# SD.net
KiCad netlist of a schematic drawn in Altium Designer
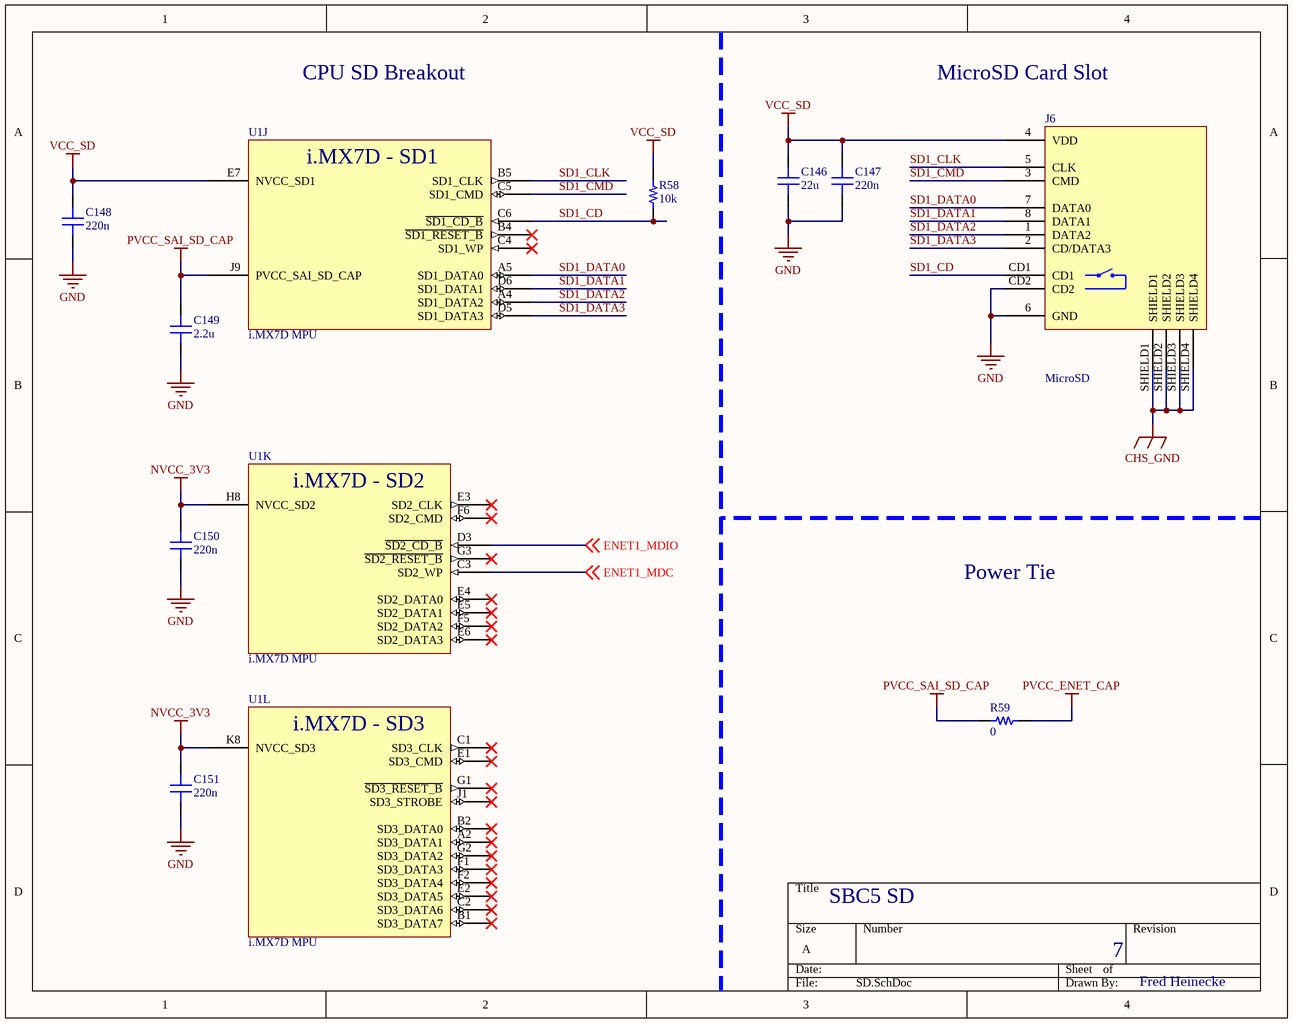
[diagram p0: SD.SchDoc]

(export (version "E")
  (design (tool "Eeschema 10.0.6"))
  (components
    (comp (ref "C146")
      (value "22u")
      (footprint "C0603")
      (description "0603 22 uF 10 V ±20% Tolerance X5R Multilayer Ceramic Chip Capacitor")
      (fields
        (field (name "MANUFACTURER") "Murata")
        (field (name "MANUFACTURER PART NUMBER") "GRM188R61A226ME15D")
      )
      (libsource (lib "SBC5") (part "GRM188R61A226ME15D"))
    )
    (comp (ref "C147")
      (value "220n")
      (footprint "C0201")
      (description "Cap Ceramic Monolithic 0.22uF 16VDC 10% SMD Paper T/R")
      (fields
        (field (name "MANUFACTURER") "Murata")
        (field (name "MANUFACTURER PART NUMBER") "GRM033R61C224KE14D")
      )
      (libsource (lib "SBC5") (part "GRM033R61C224KE14D"))
    )
    (comp (ref "C148")
      (value "220n")
      (footprint "C0201")
      (description "Cap Ceramic Monolithic 0.22uF 16VDC 10% SMD Paper T/R")
      (fields
        (field (name "MANUFACTURER") "Murata")
        (field (name "MANUFACTURER PART NUMBER") "GRM033R61C224KE14D")
      )
      (libsource (lib "SBC5") (part "GRM033R61C224KE14D"))
    )
    (comp (ref "C149")
      (value "2.2u")
      (footprint "C0402")
      (description "TAIYO YUDEN         LMK105BJ225MV-F            CERAMIC CAPACITOR, 2.2UF, 10V, X5R, 20%, 0402")
      (fields
        (field (name "MANUFACTURER") "Taiyo Yuden")
        (field (name "MANUFACTURER PART NUMBER") "LMK105BJ225MV-F")
      )
      (libsource (lib "SBC5") (part "LMK105BJ225MV-F"))
    )
    (comp (ref "C150")
      (value "220n")
      (footprint "C0201")
      (description "Cap Ceramic Monolithic 0.22uF 16VDC 10% SMD Paper T/R")
      (fields
        (field (name "MANUFACTURER") "Murata")
        (field (name "MANUFACTURER PART NUMBER") "GRM033R61C224KE14D")
      )
      (libsource (lib "SBC5") (part "GRM033R61C224KE14D"))
    )
    (comp (ref "C151")
      (value "220n")
      (footprint "C0201")
      (description "Cap Ceramic Monolithic 0.22uF 16VDC 10% SMD Paper T/R")
      (fields
        (field (name "MANUFACTURER") "Murata")
        (field (name "MANUFACTURER PART NUMBER") "GRM033R61C224KE14D")
      )
      (libsource (lib "SBC5") (part "GRM033R61C224KE14D"))
    )
    (comp (ref "J6")
      (value "MicroSD")
      (footprint "114-00841-68")
      (description "Conn; IC Socket; Micro SD; Right Angle; PCB Mount; MicroSD Ser.")
      (fields
        (field (name "MANUFACTURER") "Amphenol Commercial")
        (field (name "MANUFACTURER PART NUMBER") "1140084168")
      )
      (libsource (lib "SBC5") (part "1140084168"))
    )
    (comp (ref "R58")
      (value "10k")
      (footprint "R0201")
      (description "RES 10K OHM 1% 1/20W 0201")
      (fields
        (field (name "MANUFACTURER") "Stackpole Electronics")
        (field (name "MANUFACTURER PART NUMBER") "RMCF0201FT10K0")
      )
      (libsource (lib "SBC5") (part "RMCF0201FT10K0"))
    )
    (comp (ref "R59")
      (value "0")
      (footprint "R0402")
      (description "RES 0 OHM JUMPER 1/16W 0402")
      (fields
        (field (name "MANUFACTURER") "Stackpole Electronics")
        (field (name "MANUFACTURER PART NUMBER") "RMCF0402ZT0R00")
      )
      (libsource (lib "SBC5") (part "RMCF0402ZT0R00"))
    )
    (comp (ref "U1")
      (value "i.MX7D MPU")
      (footprint "BGA541C75P25X25_1900X1900X140")
      (description "Heterogeneous Multicore Processing Architecture")
      (fields
        (field (name "MANUFACTURER") "NXP Freescale")
        (field (name "MANUFACTURER PART NUMBER") "MCIMX7D2DVM12SD")
      )
      (libsource (lib "SBC5") (part "MCIMX7D2DVM12SD"))
    )
  )
  (nets
    (net (code "1") (name "/SD1_CD") (class "Default")
      (node (ref "J6") (pin "CD1") (pinfunction "CD1_CD1") (pintype "passive"))
      (node (ref "R58") (pin "1") (pinfunction "1_1") (pintype "passive"))
      (node (ref "U1") (pin "C6") (pinfunction "~{SD1_CD_B}_C6") (pintype "input"))
    )
    (net (code "2") (name "/SD1_CLK") (class "Default")
      (node (ref "J6") (pin "5") (pinfunction "CLK_5") (pintype "passive"))
      (node (ref "U1") (pin "B5") (pinfunction "SD1_CLK_B5") (pintype "output"))
    )
    (net (code "3") (name "/SD1_CMD") (class "Default")
      (node (ref "J6") (pin "3") (pinfunction "CMD_3") (pintype "passive"))
      (node (ref "U1") (pin "C5") (pinfunction "SD1_CMD_C5") (pintype "bidirectional"))
    )
    (net (code "4") (name "/SD1_DATA0") (class "Default")
      (node (ref "J6") (pin "7") (pinfunction "DATA0_7") (pintype "passive"))
      (node (ref "U1") (pin "A5") (pinfunction "SD1_DATA0_A5") (pintype "bidirectional"))
    )
    (net (code "5") (name "/SD1_DATA1") (class "Default")
      (node (ref "J6") (pin "8") (pinfunction "DATA1_8") (pintype "passive"))
      (node (ref "U1") (pin "D6") (pinfunction "SD1_DATA1_D6") (pintype "bidirectional"))
    )
    (net (code "6") (name "/SD1_DATA2") (class "Default")
      (node (ref "J6") (pin "1") (pinfunction "DATA2_1") (pintype "passive"))
      (node (ref "U1") (pin "A4") (pinfunction "SD1_DATA2_A4") (pintype "bidirectional"))
    )
    (net (code "7") (name "/SD1_DATA3") (class "Default")
      (node (ref "J6") (pin "2") (pinfunction "CD/DATA3_2") (pintype "passive"))
      (node (ref "U1") (pin "D5") (pinfunction "SD1_DATA3_D5") (pintype "bidirectional"))
    )
    (net (code "8") (name "CHS_GND") (class "Default")
      (node (ref "J6") (pin "SHIELD1") (pinfunction "SHIELD1_SHIELD1") (pintype "passive"))
      (node (ref "J6") (pin "SHIELD2") (pinfunction "SHIELD2_SHIELD2") (pintype "passive"))
      (node (ref "J6") (pin "SHIELD3") (pinfunction "SHIELD3_SHIELD3") (pintype "passive"))
      (node (ref "J6") (pin "SHIELD4") (pinfunction "SHIELD4_SHIELD4") (pintype "passive"))
    )
    (net (code "9") (name "ENET1_MDC") (class "Default")
      (node (ref "U1") (pin "C3") (pinfunction "SD2_WP_C3") (pintype "input"))
    )
    (net (code "10") (name "ENET1_MDIO") (class "Default")
      (node (ref "U1") (pin "D3") (pinfunction "~{SD2_CD_B}_D3") (pintype "input"))
    )
    (net (code "11") (name "GND") (class "Default")
      (node (ref "C146") (pin "1") (pinfunction "1_1") (pintype "passive"))
      (node (ref "C147") (pin "1") (pinfunction "1_1") (pintype "passive"))
      (node (ref "C148") (pin "1") (pinfunction "1_1") (pintype "passive"))
      (node (ref "C149") (pin "1") (pinfunction "1_1") (pintype "passive"))
      (node (ref "C150") (pin "1") (pinfunction "1_1") (pintype "passive"))
      (node (ref "C151") (pin "1") (pinfunction "1_1") (pintype "passive"))
      (node (ref "J6") (pin "6") (pinfunction "GND_6") (pintype "passive"))
      (node (ref "J6") (pin "CD2") (pinfunction "CD2_CD2") (pintype "passive"))
    )
    (net (code "12") (name "NVCC_3V3") (class "Default")
      (node (ref "C150") (pin "2") (pinfunction "2_2") (pintype "passive"))
      (node (ref "C151") (pin "2") (pinfunction "2_2") (pintype "passive"))
      (node (ref "U1") (pin "H8") (pinfunction "NVCC_SD2_H8") (pintype "power_in"))
      (node (ref "U1") (pin "K8") (pinfunction "NVCC_SD3_K8") (pintype "power_in"))
    )
    (net (code "13") (name "PVCC_ENET_CAP") (class "Default")
      (node (ref "R59") (pin "2") (pinfunction "2_2") (pintype "passive"))
    )
    (net (code "14") (name "PVCC_SAI_SD_CAP") (class "Default")
      (node (ref "C149") (pin "2") (pinfunction "2_2") (pintype "passive"))
      (node (ref "R59") (pin "1") (pinfunction "1_1") (pintype "passive"))
      (node (ref "U1") (pin "J9") (pinfunction "PVCC_SAI_SD_CAP_J9") (pintype "power_in"))
    )
    (net (code "15") (name "VCC_SD") (class "Default")
      (node (ref "C146") (pin "2") (pinfunction "2_2") (pintype "passive"))
      (node (ref "C147") (pin "2") (pinfunction "2_2") (pintype "passive"))
      (node (ref "C148") (pin "2") (pinfunction "2_2") (pintype "passive"))
      (node (ref "J6") (pin "4") (pinfunction "VDD_4") (pintype "passive"))
      (node (ref "R58") (pin "2") (pinfunction "2_2") (pintype "passive"))
      (node (ref "U1") (pin "E7") (pinfunction "NVCC_SD1_E7") (pintype "power_in"))
    )
    (net (code "16") (name "unconnected-(U1J-SD1_WP-PadC4)") (class "Default")
      (node (ref "U1") (pin "C4") (pinfunction "SD1_WP_C4") (pintype "input+no_connect"))
    )
    (net (code "17") (name "unconnected-(U1J-~{SD1_RESET_B}-PadB4)") (class "Default")
      (node (ref "U1") (pin "B4") (pinfunction "~{SD1_RESET_B}_B4") (pintype "output+no_connect"))
    )
    (net (code "18") (name "unconnected-(U1K-SD2_CLK-PadE3)") (class "Default")
      (node (ref "U1") (pin "E3") (pinfunction "SD2_CLK_E3") (pintype "output+no_connect"))
    )
    (net (code "19") (name "unconnected-(U1K-SD2_CMD-PadF6)") (class "Default")
      (node (ref "U1") (pin "F6") (pinfunction "SD2_CMD_F6") (pintype "bidirectional+no_connect"))
    )
    (net (code "20") (name "unconnected-(U1K-SD2_DATA0-PadE4)") (class "Default")
      (node (ref "U1") (pin "E4") (pinfunction "SD2_DATA0_E4") (pintype "bidirectional+no_connect"))
    )
    (net (code "21") (name "unconnected-(U1K-SD2_DATA1-PadE5)") (class "Default")
      (node (ref "U1") (pin "E5") (pinfunction "SD2_DATA1_E5") (pintype "bidirectional+no_connect"))
    )
    (net (code "22") (name "unconnected-(U1K-SD2_DATA2-PadF5)") (class "Default")
      (node (ref "U1") (pin "F5") (pinfunction "SD2_DATA2_F5") (pintype "bidirectional+no_connect"))
    )
    (net (code "23") (name "unconnected-(U1K-SD2_DATA3-PadE6)") (class "Default")
      (node (ref "U1") (pin "E6") (pinfunction "SD2_DATA3_E6") (pintype "bidirectional+no_connect"))
    )
    (net (code "24") (name "unconnected-(U1K-~{SD2_RESET_B}-PadG3)") (class "Default")
      (node (ref "U1") (pin "G3") (pinfunction "~{SD2_RESET_B}_G3") (pintype "output+no_connect"))
    )
    (net (code "25") (name "unconnected-(U1L-SD3_CLK-PadC1)") (class "Default")
      (node (ref "U1") (pin "C1") (pinfunction "SD3_CLK_C1") (pintype "output+no_connect"))
    )
    (net (code "26") (name "unconnected-(U1L-SD3_CMD-PadE1)") (class "Default")
      (node (ref "U1") (pin "E1") (pinfunction "SD3_CMD_E1") (pintype "bidirectional+no_connect"))
    )
    (net (code "27") (name "unconnected-(U1L-SD3_DATA0-PadB2)") (class "Default")
      (node (ref "U1") (pin "B2") (pinfunction "SD3_DATA0_B2") (pintype "bidirectional+no_connect"))
    )
    (net (code "28") (name "unconnected-(U1L-SD3_DATA1-PadA2)") (class "Default")
      (node (ref "U1") (pin "A2") (pinfunction "SD3_DATA1_A2") (pintype "bidirectional+no_connect"))
    )
    (net (code "29") (name "unconnected-(U1L-SD3_DATA2-PadG2)") (class "Default")
      (node (ref "U1") (pin "G2") (pinfunction "SD3_DATA2_G2") (pintype "bidirectional+no_connect"))
    )
    (net (code "30") (name "unconnected-(U1L-SD3_DATA3-PadF1)") (class "Default")
      (node (ref "U1") (pin "F1") (pinfunction "SD3_DATA3_F1") (pintype "bidirectional+no_connect"))
    )
    (net (code "31") (name "unconnected-(U1L-SD3_DATA4-PadF2)") (class "Default")
      (node (ref "U1") (pin "F2") (pinfunction "SD3_DATA4_F2") (pintype "bidirectional+no_connect"))
    )
    (net (code "32") (name "unconnected-(U1L-SD3_DATA5-PadE2)") (class "Default")
      (node (ref "U1") (pin "E2") (pinfunction "SD3_DATA5_E2") (pintype "bidirectional+no_connect"))
    )
    (net (code "33") (name "unconnected-(U1L-SD3_DATA6-PadC2)") (class "Default")
      (node (ref "U1") (pin "C2") (pinfunction "SD3_DATA6_C2") (pintype "bidirectional+no_connect"))
    )
    (net (code "34") (name "unconnected-(U1L-SD3_DATA7-PadB1)") (class "Default")
      (node (ref "U1") (pin "B1") (pinfunction "SD3_DATA7_B1") (pintype "bidirectional+no_connect"))
    )
    (net (code "35") (name "unconnected-(U1L-SD3_STROBE-PadJ1)") (class "Default")
      (node (ref "U1") (pin "J1") (pinfunction "SD3_STROBE_J1") (pintype "bidirectional+no_connect"))
    )
    (net (code "36") (name "unconnected-(U1L-~{SD3_RESET_B}-PadG1)") (class "Default")
      (node (ref "U1") (pin "G1") (pinfunction "~{SD3_RESET_B}_G1") (pintype "output+no_connect"))
    )
  )
)
